# Transmitter.net
KiCad netlist of a schematic drawn in Altium Designer
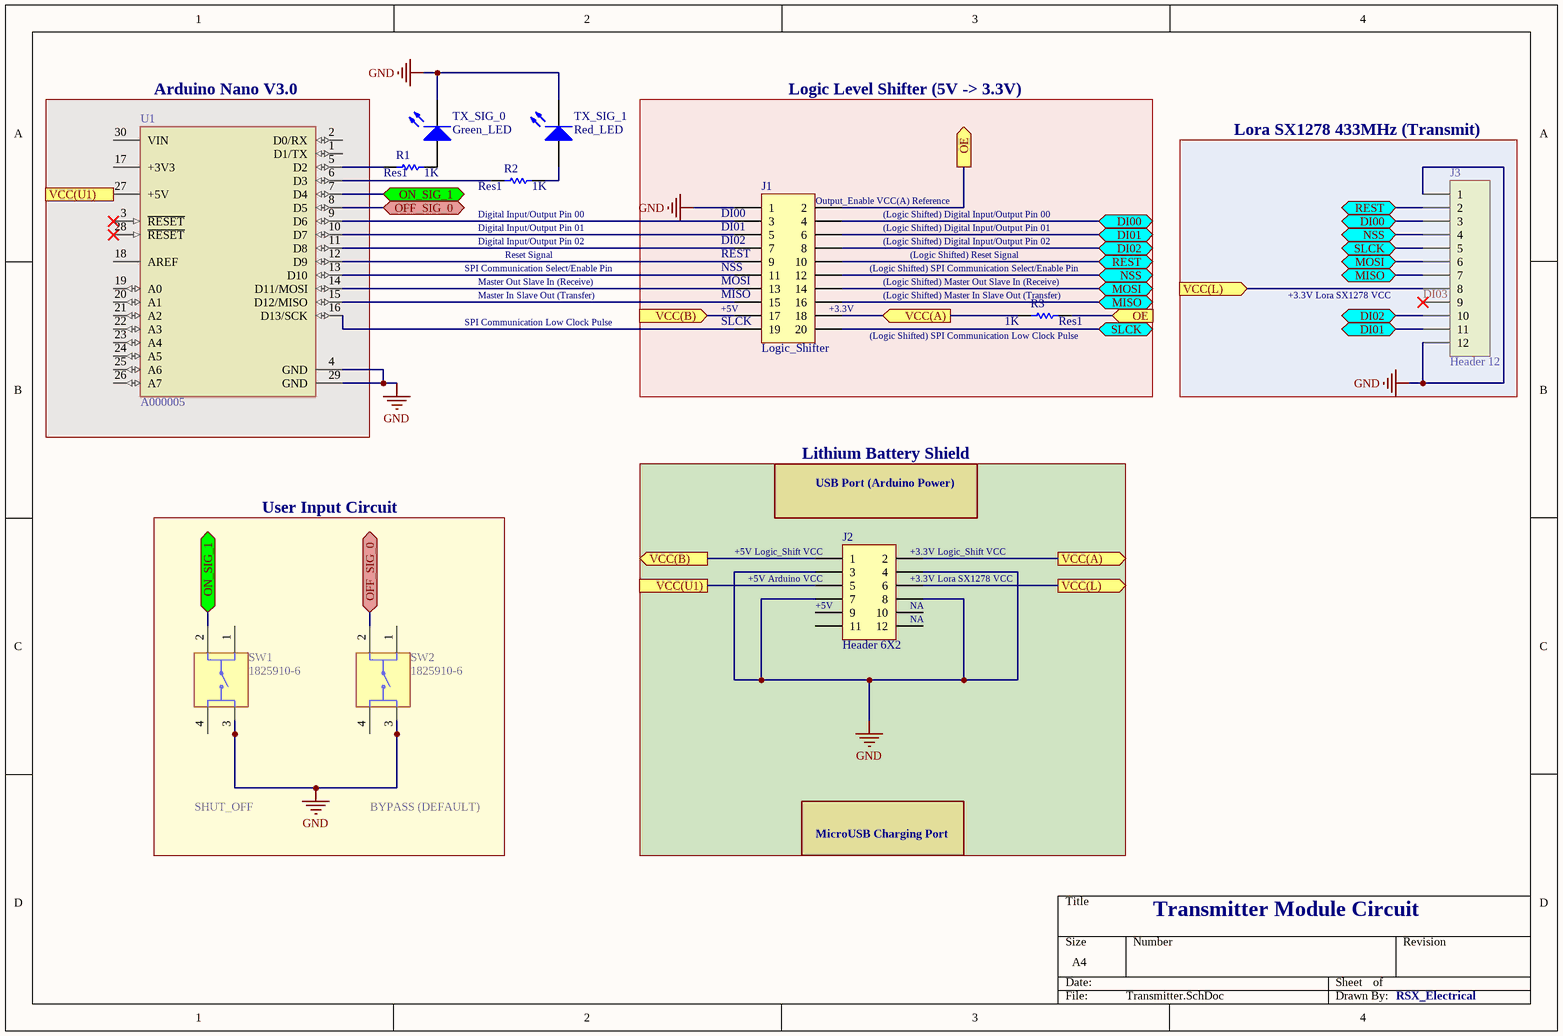
[diagram p0: Transmitter.SchDoc]

(export (version "E")
  (design (tool "Eeschema 10.0.6"))
  (components
    (comp (ref "J1")
      (value "Logic_Shifter")
      (footprint "Logic SHifter")
      (description "Header, 10-Pin, Dual row")
      (fields (field (name "PUBLISHER") "Altium Limited"))
      (libsource (lib "Miscellaneous Connectors") (part "Header 10X2"))
    )
    (comp (ref "J2")
      (value "Header 6X2")
      (footprint "Transmitter_PCB:3.3V/5V Battery Shield - duplicate")
      (description "Header, 6-Pin, Dual row")
      (fields (field (name "PUBLISHER") "Altium Limited"))
      (libsource (lib "Miscellaneous Connectors") (part "Header 6X2"))
    )
    (comp (ref "J3")
      (value "Header 12")
      (footprint "Transmitter_PCB:LORA Sx1278")
      (description "Header, 12-Pin")
      (fields (field (name "PUBLISHER") "Altium Limited"))
      (libsource (lib "Miscellaneous Connectors") (part "Header 12"))
    )
    (comp (ref "R1")
      (value "Res1")
      (footprint "AXIAL-0.3")
      (description "Resistor")
      (fields (field (name "ALTIUM_VALUE") "1K") (field (name "PUBLISHER") "Altium Limited"))
      (libsource (lib "Miscellaneous Devices") (part "Res1"))
    )
    (comp (ref "R2")
      (value "Res1")
      (footprint "AXIAL-0.3")
      (description "Resistor")
      (fields (field (name "ALTIUM_VALUE") "1K") (field (name "PUBLISHER") "Altium Limited"))
      (libsource (lib "Miscellaneous Devices") (part "Res1"))
    )
    (comp (ref "R3")
      (value "Res1")
      (footprint "AXIAL-0.3")
      (description "Resistor")
      (fields (field (name "ALTIUM_VALUE") "1K") (field (name "PUBLISHER") "Altium Limited"))
      (libsource (lib "Miscellaneous Devices") (part "Res1"))
    )
    (comp (ref "SW1")
      (value "1825910-6")
      (footprint "SW_1825910-6-4")
      (description "Switch Tactile OFF (ON) SPST Round Button PC Pins 0.05A 24VDC 100000Cycles 1.57N Thru-Hole Loose")
      (libsource (lib "1825910-6") (part "1825910-6"))
    )
    (comp (ref "SW2")
      (value "1825910-6")
      (footprint "SW_1825910-6-4")
      (description "Switch Tactile OFF (ON) SPST Round Button PC Pins 0.05A 24VDC 100000Cycles 1.57N Thru-Hole Loose")
      (libsource (lib "1825910-6") (part "1825910-6"))
    )
    (comp (ref "TX_SIG_0")
      (value "Green_LED")
      (footprint "LED-0")
      (description "Typical INFRARED GaAs LED")
      (fields (field (name "PUBLISHER") "Altium Limited"))
      (libsource (lib "Miscellaneous Devices") (part "LED0"))
    )
    (comp (ref "TX_SIG_1")
      (value "Red_LED")
      (footprint "LED-0")
      (description "Typical INFRARED GaAs LED")
      (fields (field (name "PUBLISHER") "Altium Limited"))
      (libsource (lib "Miscellaneous Devices") (part "LED0"))
    )
    (comp (ref "U1")
      (value "A000005")
      (footprint "FP-A000005-MFG")
      (description "ARDUINO NANO ATMEGA328 EVAL BRD")
      (libsource (lib "Altium Content Vault") (part "d190c066e99afd1c6882cf92e11b2cc"))
    )
  )
  (nets
    (net (code "2") (name "/DI00") (class "Default")
      (node (ref "J1") (pin "4") (pinfunction "4_4") (pintype "passive"))
      (node (ref "J3") (pin "3") (pinfunction "3_3") (pintype "passive"))
    )
    (net (code "3") (name "/DI01") (class "Default")
      (node (ref "J1") (pin "6") (pinfunction "6_6") (pintype "passive"))
      (node (ref "J3") (pin "11") (pinfunction "11_11") (pintype "passive"))
    )
    (net (code "4") (name "/DI02") (class "Default")
      (node (ref "J1") (pin "8") (pinfunction "8_8") (pintype "passive"))
      (node (ref "J3") (pin "10") (pinfunction "10_10") (pintype "passive"))
    )
    (net (code "5") (name "/DI03") (class "Default")
      (node (ref "J3") (pin "9") (pinfunction "9_9") (pintype "passive+no_connect"))
    )
    (net (code "6") (name "/MISO") (class "Default")
      (node (ref "J1") (pin "16") (pinfunction "16_16") (pintype "passive"))
      (node (ref "J3") (pin "7") (pinfunction "7_7") (pintype "passive"))
    )
    (net (code "7") (name "/MOSI") (class "Default")
      (node (ref "J1") (pin "14") (pinfunction "14_14") (pintype "passive"))
      (node (ref "J3") (pin "6") (pinfunction "6_6") (pintype "passive"))
    )
    (net (code "8") (name "/NSS") (class "Default")
      (node (ref "J1") (pin "12") (pinfunction "12_12") (pintype "passive"))
      (node (ref "J3") (pin "4") (pinfunction "4_4") (pintype "passive"))
    )
    (net (code "9") (name "/OE") (class "Default")
      (node (ref "J1") (pin "2") (pinfunction "2_2") (pintype "passive"))
      (node (ref "R3") (pin "1") (pinfunction "1_1") (pintype "passive"))
    )
    (net (code "10") (name "/OFF_SIG_0") (class "Default")
      (node (ref "SW2") (pin "2") (pinfunction "2_2") (pintype "passive"))
      (node (ref "U1") (pin "8") (pinfunction "D5_8") (pintype "bidirectional"))
    )
    (net (code "11") (name "/ON_SIG_1") (class "Default")
      (node (ref "SW1") (pin "2") (pinfunction "2_2") (pintype "passive"))
      (node (ref "U1") (pin "7") (pinfunction "D4_7") (pintype "bidirectional"))
    )
    (net (code "12") (name "/REST") (class "Default")
      (node (ref "J1") (pin "10") (pinfunction "10_10") (pintype "passive"))
      (node (ref "J3") (pin "2") (pinfunction "2_2") (pintype "passive"))
    )
    (net (code "13") (name "/SLCK") (class "Default")
      (node (ref "J1") (pin "20") (pinfunction "20_20") (pintype "passive"))
      (node (ref "J3") (pin "5") (pinfunction "5_5") (pintype "passive"))
    )
    (net (code "14") (name "/VCC(A)") (class "Default")
      (node (ref "J1") (pin "18") (pinfunction "18_18") (pintype "passive"))
      (node (ref "J2") (pin "2") (pinfunction "2_2") (pintype "passive"))
      (node (ref "R3") (pin "2") (pinfunction "2_2") (pintype "passive"))
    )
    (net (code "15") (name "/VCC(B)") (class "Default")
      (node (ref "J1") (pin "17") (pinfunction "17_17") (pintype "passive"))
      (node (ref "J2") (pin "1") (pinfunction "1_1") (pintype "passive"))
    )
    (net (code "16") (name "/VCC(L)") (class "Default")
      (node (ref "J2") (pin "6") (pinfunction "6_6") (pintype "passive"))
      (node (ref "J3") (pin "8") (pinfunction "8_8") (pintype "passive"))
    )
    (net (code "17") (name "/VCC(U1)") (class "Default")
      (node (ref "J2") (pin "5") (pinfunction "5_5") (pintype "passive"))
      (node (ref "U1") (pin "27") (pinfunction "+5V_27") (pintype "power_in"))
    )
    (net (code "18") (name "GND") (class "Default")
      (node (ref "J1") (pin "1") (pinfunction "1_1") (pintype "passive"))
      (node (ref "J2") (pin "3") (pinfunction "3_3") (pintype "passive"))
      (node (ref "J2") (pin "4") (pinfunction "4_4") (pintype "passive"))
      (node (ref "J2") (pin "7") (pinfunction "7_7") (pintype "passive"))
      (node (ref "J2") (pin "8") (pinfunction "8_8") (pintype "passive"))
      (node (ref "J3") (pin "1") (pinfunction "1_1") (pintype "passive"))
      (node (ref "J3") (pin "12") (pinfunction "12_12") (pintype "passive"))
      (node (ref "SW1") (pin "3") (pinfunction "3_3") (pintype "passive"))
      (node (ref "SW2") (pin "3") (pinfunction "3_3") (pintype "passive"))
      (node (ref "TX_SIG_0") (pin "2") (pinfunction "K_2") (pintype "passive"))
      (node (ref "TX_SIG_1") (pin "2") (pinfunction "K_2") (pintype "passive"))
      (node (ref "U1") (pin "29") (pinfunction "GND_29") (pintype "power_in"))
      (node (ref "U1") (pin "4") (pinfunction "GND_4") (pintype "power_in"))
    )
    (net (code "19") (name "Net-(TX_SIG_0-A)") (class "Default")
      (node (ref "R1") (pin "1") (pinfunction "1_1") (pintype "passive"))
      (node (ref "TX_SIG_0") (pin "1") (pinfunction "A_1") (pintype "passive"))
    )
    (net (code "20") (name "Net-(TX_SIG_1-A)") (class "Default")
      (node (ref "R2") (pin "1") (pinfunction "1_1") (pintype "passive"))
      (node (ref "TX_SIG_1") (pin "1") (pinfunction "A_1") (pintype "passive"))
    )
    (net (code "21") (name "Net-(U1-D2)") (class "Default")
      (node (ref "R1") (pin "2") (pinfunction "2_2") (pintype "passive"))
      (node (ref "U1") (pin "5") (pinfunction "D2_5") (pintype "bidirectional"))
    )
    (net (code "22") (name "Net-(U1-D3)") (class "Default")
      (node (ref "R2") (pin "2") (pinfunction "2_2") (pintype "passive"))
      (node (ref "U1") (pin "6") (pinfunction "D3_6") (pintype "bidirectional"))
    )
    (net (code "23") (name "Net-(U1-D6)") (class "Default")
      (node (ref "J1") (pin "3") (pinfunction "3_3") (pintype "passive"))
      (node (ref "U1") (pin "9") (pinfunction "D6_9") (pintype "bidirectional"))
    )
    (net (code "24") (name "Net-(U1-D7)") (class "Default")
      (node (ref "J1") (pin "5") (pinfunction "5_5") (pintype "passive"))
      (node (ref "U1") (pin "10") (pinfunction "D7_10") (pintype "bidirectional"))
    )
    (net (code "25") (name "Net-(U1-D8)") (class "Default")
      (node (ref "J1") (pin "7") (pinfunction "7_7") (pintype "passive"))
      (node (ref "U1") (pin "11") (pinfunction "D8_11") (pintype "bidirectional"))
    )
    (net (code "26") (name "Net-(U1-D9)") (class "Default")
      (node (ref "J1") (pin "9") (pinfunction "9_9") (pintype "passive"))
      (node (ref "U1") (pin "12") (pinfunction "D9_12") (pintype "bidirectional"))
    )
    (net (code "27") (name "Net-(U1-D10)") (class "Default")
      (node (ref "J1") (pin "11") (pinfunction "11_11") (pintype "passive"))
      (node (ref "U1") (pin "13") (pinfunction "D10_13") (pintype "bidirectional"))
    )
    (net (code "28") (name "Net-(U1-D11{slash}MOSI)") (class "Default")
      (node (ref "J1") (pin "13") (pinfunction "13_13") (pintype "passive"))
      (node (ref "U1") (pin "14") (pinfunction "D11/MOSI_14") (pintype "bidirectional"))
    )
    (net (code "29") (name "Net-(U1-D12{slash}MISO)") (class "Default")
      (node (ref "J1") (pin "15") (pinfunction "15_15") (pintype "passive"))
      (node (ref "U1") (pin "15") (pinfunction "D12/MISO_15") (pintype "bidirectional"))
    )
    (net (code "30") (name "Net-(U1-D13{slash}SCK)") (class "Default")
      (node (ref "J1") (pin "19") (pinfunction "19_19") (pintype "passive"))
      (node (ref "U1") (pin "16") (pinfunction "D13/SCK_16") (pintype "bidirectional"))
    )
    (net (code "31") (name "unconnected-(J2-Pad9)") (class "Default")
      (node (ref "J2") (pin "9") (pinfunction "9_9") (pintype "passive"))
    )
    (net (code "32") (name "unconnected-(J2-Pad10)") (class "Default")
      (node (ref "J2") (pin "10") (pinfunction "10_10") (pintype "passive"))
    )
    (net (code "33") (name "unconnected-(J2-Pad11)") (class "Default")
      (node (ref "J2") (pin "11") (pinfunction "11_11") (pintype "passive"))
    )
    (net (code "34") (name "unconnected-(J2-Pad12)") (class "Default")
      (node (ref "J2") (pin "12") (pinfunction "12_12") (pintype "passive"))
    )
    (net (code "35") (name "unconnected-(SW1-Pad1)") (class "Default")
      (node (ref "SW1") (pin "1") (pinfunction "1_1") (pintype "passive"))
    )
    (net (code "36") (name "unconnected-(SW1-Pad4)") (class "Default")
      (node (ref "SW1") (pin "4") (pinfunction "4_4") (pintype "passive"))
    )
    (net (code "37") (name "unconnected-(SW2-Pad1)") (class "Default")
      (node (ref "SW2") (pin "1") (pinfunction "1_1") (pintype "passive"))
    )
    (net (code "38") (name "unconnected-(SW2-Pad4)") (class "Default")
      (node (ref "SW2") (pin "4") (pinfunction "4_4") (pintype "passive"))
    )
    (net (code "39") (name "unconnected-(U1-+3V3-Pad17)") (class "Default")
      (node (ref "U1") (pin "17") (pinfunction "+3V3_17") (pintype "power_in"))
    )
    (net (code "40") (name "unconnected-(U1-A0-Pad19)") (class "Default")
      (node (ref "U1") (pin "19") (pinfunction "A0_19") (pintype "bidirectional"))
    )
    (net (code "41") (name "unconnected-(U1-A1-Pad20)") (class "Default")
      (node (ref "U1") (pin "20") (pinfunction "A1_20") (pintype "bidirectional"))
    )
    (net (code "42") (name "unconnected-(U1-A2-Pad21)") (class "Default")
      (node (ref "U1") (pin "21") (pinfunction "A2_21") (pintype "bidirectional"))
    )
    (net (code "43") (name "unconnected-(U1-A3-Pad22)") (class "Default")
      (node (ref "U1") (pin "22") (pinfunction "A3_22") (pintype "bidirectional"))
    )
    (net (code "44") (name "unconnected-(U1-A4-Pad23)") (class "Default")
      (node (ref "U1") (pin "23") (pinfunction "A4_23") (pintype "bidirectional"))
    )
    (net (code "45") (name "unconnected-(U1-A5-Pad24)") (class "Default")
      (node (ref "U1") (pin "24") (pinfunction "A5_24") (pintype "bidirectional"))
    )
    (net (code "46") (name "unconnected-(U1-A6-Pad25)") (class "Default")
      (node (ref "U1") (pin "25") (pinfunction "A6_25") (pintype "bidirectional"))
    )
    (net (code "47") (name "unconnected-(U1-A7-Pad26)") (class "Default")
      (node (ref "U1") (pin "26") (pinfunction "A7_26") (pintype "bidirectional"))
    )
    (net (code "48") (name "unconnected-(U1-AREF-Pad18)") (class "Default")
      (node (ref "U1") (pin "18") (pinfunction "AREF_18") (pintype "passive"))
    )
    (net (code "49") (name "unconnected-(U1-D0{slash}RX-Pad2)") (class "Default")
      (node (ref "U1") (pin "2") (pinfunction "D0/RX_2") (pintype "bidirectional"))
    )
    (net (code "50") (name "unconnected-(U1-D1{slash}TX-Pad1)") (class "Default")
      (node (ref "U1") (pin "1") (pinfunction "D1/TX_1") (pintype "bidirectional"))
    )
    (net (code "51") (name "unconnected-(U1-VIN-Pad30)") (class "Default")
      (node (ref "U1") (pin "30") (pinfunction "VIN_30") (pintype "power_in"))
    )
    (net (code "52") (name "unconnected-(U1-~{RESET}-Pad3)") (class "Default")
      (node (ref "U1") (pin "3") (pinfunction "~{RESET}_3") (pintype "input+no_connect"))
    )
    (net (code "53") (name "unconnected-(U1-~{RESET}-Pad28)") (class "Default")
      (node (ref "U1") (pin "28") (pinfunction "~{RESET}_28") (pintype "input+no_connect"))
    )
  )
)
